# FFT_Device.net
KiCad netlist of a schematic drawn in Altium Designer
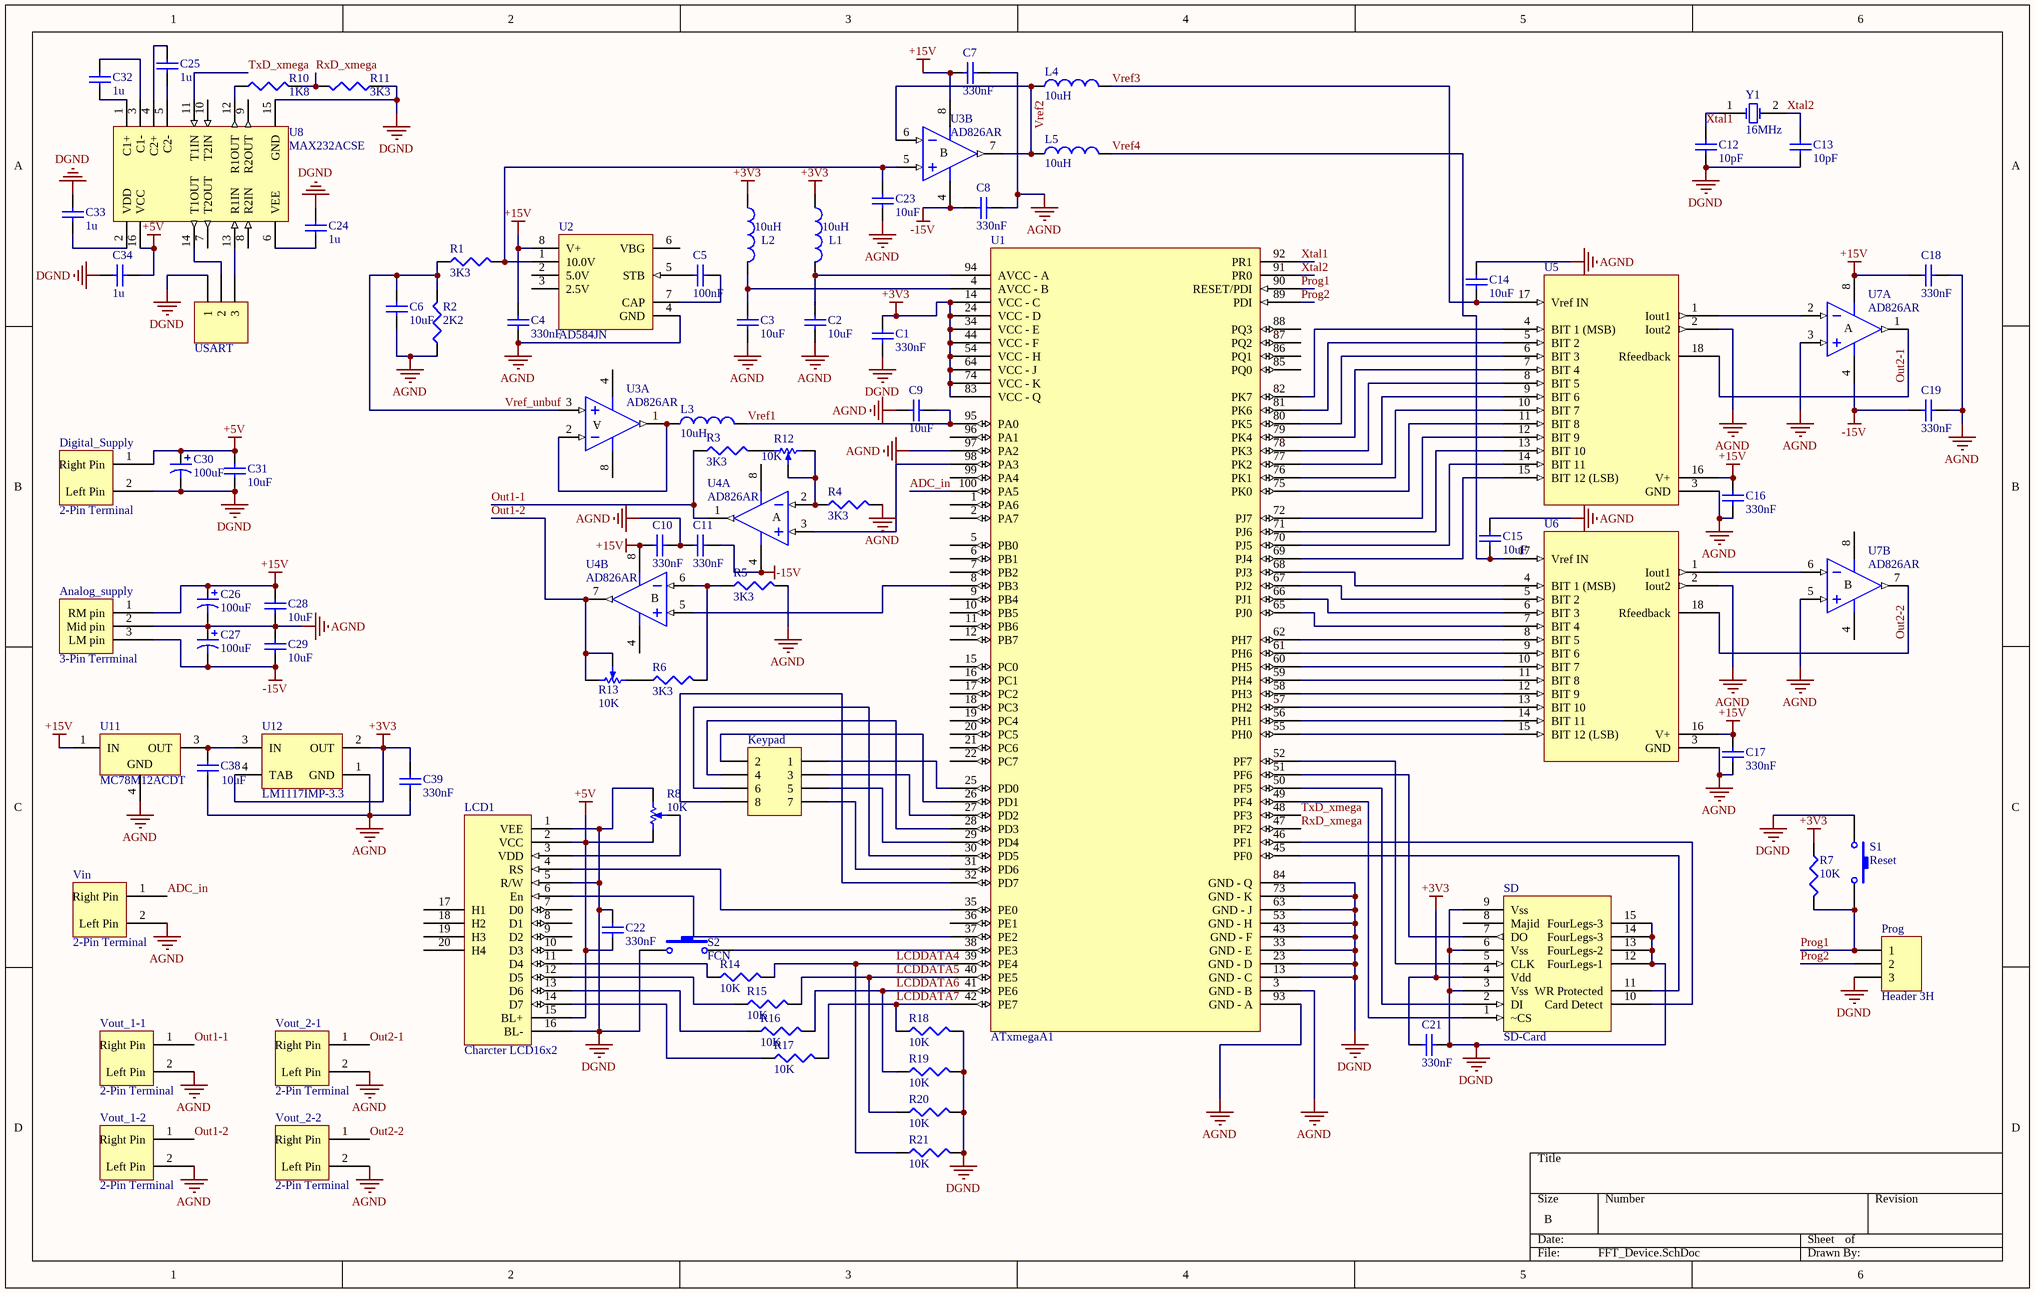
[diagram p0: FFT_Device.SchDoc]

(export (version "E")
  (design (tool "Eeschema 10.0.6"))
  (components
    (comp (ref "Analog_supply")
      (value "3-Pin Terrminal")
      (footprint "3-pin Terminal")
      (libsource (lib "MyLib") (part "3-Pin Terrminal"))
    )
    (comp (ref "C1")
      (value "330nF")
      (footprint "MELF-R3216-1206")
      (description "Capacitor (Semiconductor SIM Model)")
      (fields (field (name "Comment") "Cap Semi"))
      (libsource (lib "Miscellaneous Devices") (part "Cap Semi"))
    )
    (comp (ref "C2")
      (value "10uF")
      (footprint "MELF-R3216-1206")
      (description "Capacitor (Semiconductor SIM Model)")
      (fields (field (name "Comment") "Cap Semi"))
      (libsource (lib "Miscellaneous Devices") (part "Cap Semi"))
    )
    (comp (ref "C3")
      (value "10uF")
      (footprint "MELF-R3216-1206")
      (description "Capacitor (Semiconductor SIM Model)")
      (fields (field (name "Comment") "Cap Semi"))
      (libsource (lib "Miscellaneous Devices") (part "Cap Semi"))
    )
    (comp (ref "C4")
      (value "330nF")
      (footprint "MELF-R3216-1206")
      (description "Capacitor (Semiconductor SIM Model)")
      (fields (field (name "Comment") "Cap Semi"))
      (libsource (lib "") (part "Cap Semi_1"))
    )
    (comp (ref "C5")
      (value "100nF")
      (footprint "MELF-R3216-1206")
      (description "Capacitor (Semiconductor SIM Model)")
      (fields (field (name "Comment") "Cap Semi"))
      (libsource (lib "Miscellaneous Devices") (part "Cap Semi"))
    )
    (comp (ref "C6")
      (value "10uF")
      (footprint "MELF-R3216-1206")
      (description "Capacitor (Semiconductor SIM Model)")
      (fields (field (name "Comment") "Cap Semi"))
      (libsource (lib "") (part "Cap Semi_1"))
    )
    (comp (ref "C7")
      (value "330nF")
      (footprint "MELF-R3216-1206")
      (description "Capacitor (Semiconductor SIM Model)")
      (fields (field (name "Comment") "Cap Semi"))
      (libsource (lib "Miscellaneous Devices") (part "Cap Semi"))
    )
    (comp (ref "C8")
      (value "330nF")
      (footprint "MELF-R3216-1206")
      (description "Capacitor (Semiconductor SIM Model)")
      (fields (field (name "Comment") "Cap Semi"))
      (libsource (lib "Miscellaneous Devices") (part "Cap Semi"))
    )
    (comp (ref "C9")
      (value "10uF")
      (footprint "MELF-R3216-1206")
      (description "Capacitor (Semiconductor SIM Model)")
      (fields (field (name "Comment") "Cap Semi"))
      (libsource (lib "Miscellaneous Devices") (part "Cap Semi"))
    )
    (comp (ref "C10")
      (value "330nF")
      (footprint "MELF-R3216-1206")
      (description "Capacitor (Semiconductor SIM Model)")
      (fields (field (name "Comment") "Cap Semi"))
      (libsource (lib "Miscellaneous Devices") (part "Cap Semi"))
    )
    (comp (ref "C11")
      (value "330nF")
      (footprint "MELF-R3216-1206")
      (description "Capacitor (Semiconductor SIM Model)")
      (fields (field (name "Comment") "Cap Semi"))
      (libsource (lib "Miscellaneous Devices") (part "Cap Semi"))
    )
    (comp (ref "C12")
      (value "10pF")
      (footprint "MELF-R3216-1206")
      (description "Capacitor (Semiconductor SIM Model)")
      (fields (field (name "Comment") "Cap Semi"))
      (libsource (lib "Miscellaneous Devices") (part "Cap Semi"))
    )
    (comp (ref "C13")
      (value "10pF")
      (footprint "MELF-R3216-1206")
      (description "Capacitor (Semiconductor SIM Model)")
      (fields (field (name "Comment") "Cap Semi"))
      (libsource (lib "Miscellaneous Devices") (part "Cap Semi"))
    )
    (comp (ref "C14")
      (value "10uF")
      (footprint "MELF-R3216-1206")
      (description "Capacitor (Semiconductor SIM Model)")
      (fields (field (name "Comment") "Cap Semi"))
      (libsource (lib "") (part "Cap Semi_1"))
    )
    (comp (ref "C15")
      (value "10uF")
      (footprint "MELF-R3216-1206")
      (description "Capacitor (Semiconductor SIM Model)")
      (fields (field (name "Comment") "Cap Semi"))
      (libsource (lib "") (part "Cap Semi_1"))
    )
    (comp (ref "C16")
      (value "330nF")
      (footprint "MELF-R3216-1206")
      (description "Capacitor (Semiconductor SIM Model)")
      (fields (field (name "Comment") "Cap Semi"))
      (libsource (lib "Miscellaneous Devices") (part "Cap Semi"))
    )
    (comp (ref "C17")
      (value "330nF")
      (footprint "MELF-R3216-1206")
      (description "Capacitor (Semiconductor SIM Model)")
      (fields (field (name "Comment") "Cap Semi"))
      (libsource (lib "Miscellaneous Devices") (part "Cap Semi"))
    )
    (comp (ref "C18")
      (value "330nF")
      (footprint "MELF-R3216-1206")
      (description "Capacitor (Semiconductor SIM Model)")
      (fields (field (name "Comment") "Cap Semi"))
      (libsource (lib "Miscellaneous Devices") (part "Cap Semi"))
    )
    (comp (ref "C19")
      (value "330nF")
      (footprint "MELF-R3216-1206")
      (description "Capacitor (Semiconductor SIM Model)")
      (fields (field (name "Comment") "Cap Semi"))
      (libsource (lib "Miscellaneous Devices") (part "Cap Semi"))
    )
    (comp (ref "C21")
      (value "330nF")
      (footprint "MELF-R3216-1206")
      (description "Capacitor (Semiconductor SIM Model)")
      (fields (field (name "Comment") "Cap Semi"))
      (libsource (lib "Miscellaneous Devices") (part "Cap Semi"))
    )
    (comp (ref "C22")
      (value "330nF")
      (footprint "MELF-R3216-1206")
      (description "Capacitor (Semiconductor SIM Model)")
      (fields (field (name "Comment") "Cap Semi"))
      (libsource (lib "Miscellaneous Devices") (part "Cap Semi"))
    )
    (comp (ref "C23")
      (value "10uF")
      (footprint "MELF-R3216-1206")
      (description "Capacitor (Semiconductor SIM Model)")
      (fields (field (name "Comment") "Cap Semi"))
      (libsource (lib "") (part "Cap Semi_1"))
    )
    (comp (ref "C24")
      (value "1u")
      (footprint "MELF-R3216-1206")
      (description "Capacitor (Semiconductor SIM Model)")
      (fields (field (name "Comment") "Cap Semi"))
      (libsource (lib "Miscellaneous Devices") (part "Cap Semi"))
    )
    (comp (ref "C25")
      (value "1u")
      (footprint "MELF-R3216-1206")
      (description "Capacitor (Semiconductor SIM Model)")
      (fields (field (name "Comment") "Cap Semi"))
      (libsource (lib "Miscellaneous Devices") (part "Cap Semi"))
    )
    (comp (ref "C26") (value "100uF") (footprint "Cap Pole-100u") (libsource (lib "MyLib") (part "Cap Pole")))
    (comp (ref "C27") (value "100uF") (footprint "Cap Pole-100u") (libsource (lib "MyLib") (part "Cap Pole")))
    (comp (ref "C28")
      (value "10uF")
      (footprint "CAPTANT100u")
      (description "Capacitor (Semiconductor SIM Model)")
      (fields (field (name "Comment") "Cap Semi"))
      (libsource (lib "Miscellaneous Devices") (part "Cap Semi"))
    )
    (comp (ref "C29")
      (value "10uF")
      (footprint "CAPTANT100u")
      (description "Capacitor (Semiconductor SIM Model)")
      (fields (field (name "Comment") "Cap Semi"))
      (libsource (lib "Miscellaneous Devices") (part "Cap Semi"))
    )
    (comp (ref "C30") (value "100uF") (footprint "Cap Pole-100u") (libsource (lib "MyLib") (part "Cap Pole")))
    (comp (ref "C31")
      (value "10uF")
      (footprint "CAPTANT100u")
      (description "Capacitor (Semiconductor SIM Model)")
      (fields (field (name "Comment") "Cap Semi"))
      (libsource (lib "Miscellaneous Devices") (part "Cap Semi"))
    )
    (comp (ref "C32")
      (value "1u")
      (footprint "MELF-R3216-1206")
      (description "Capacitor (Semiconductor SIM Model)")
      (fields (field (name "Comment") "Cap Semi"))
      (libsource (lib "Miscellaneous Devices") (part "Cap Semi"))
    )
    (comp (ref "C33")
      (value "1u")
      (footprint "MELF-R3216-1206")
      (description "Capacitor (Semiconductor SIM Model)")
      (fields (field (name "Comment") "Cap Semi"))
      (libsource (lib "Miscellaneous Devices") (part "Cap Semi"))
    )
    (comp (ref "C34")
      (value "1u")
      (footprint "MELF-R3216-1206")
      (description "Capacitor (Semiconductor SIM Model)")
      (fields (field (name "Comment") "Cap Semi"))
      (libsource (lib "Miscellaneous Devices") (part "Cap Semi"))
    )
    (comp (ref "C38")
      (value "10uF")
      (footprint "MELF-R3216-1206")
      (description "Capacitor (Semiconductor SIM Model)")
      (fields (field (name "Comment") "Cap Semi"))
      (libsource (lib "Miscellaneous Devices") (part "Cap Semi"))
    )
    (comp (ref "C39")
      (value "330nF")
      (footprint "MELF-R3216-1206")
      (description "Capacitor (Semiconductor SIM Model)")
      (fields (field (name "Comment") "Cap Semi"))
      (libsource (lib "Miscellaneous Devices") (part "Cap Semi"))
    )
    (comp (ref "Digital_Supply")
      (value "2-Pin Terminal")
      (footprint "2-pin Terminal")
      (libsource (lib "MyLib") (part "2-Pin Terminal"))
    )
    (comp (ref "Keypad")
      (value "Header 4X2")
      (footprint "HDR2X4")
      (description "Header, 4-Pin, Dual row")
      (libsource (lib "Miscellaneous Connectors") (part "Header 4X2"))
    )
    (comp (ref "L1")
      (value "10uH")
      (footprint "MELF-R3216-1206")
      (description "Inductor")
      (libsource (lib "") (part "Inductor_1"))
    )
    (comp (ref "L2")
      (value "10uH")
      (footprint "MELF-R3216-1206")
      (description "Inductor")
      (libsource (lib "") (part "Inductor_1"))
    )
    (comp (ref "L3")
      (value "10uH")
      (footprint "MELF-R3216-1206")
      (description "Inductor")
      (libsource (lib "Miscellaneous Devices") (part "Inductor"))
    )
    (comp (ref "L4")
      (value "10uH")
      (footprint "MELF-R3216-1206")
      (description "Inductor")
      (libsource (lib "Miscellaneous Devices") (part "Inductor"))
    )
    (comp (ref "L5")
      (value "10uH")
      (footprint "MELF-R3216-1206")
      (description "Inductor")
      (libsource (lib "Miscellaneous Devices") (part "Inductor"))
    )
    (comp (ref "LCD1")
      (value "Charcter LCD16x2")
      (footprint "LCD16x2")
      (libsource (lib "MyLib") (part "LCD16x2"))
    )
    (comp (ref "Prog")
      (value "Header 3H")
      (footprint "HDR1X3H")
      (description "Header, 3-Pin, Right Angle")
      (libsource (lib "Miscellaneous Connectors") (part "Header 3H"))
    )
    (comp (ref "R1")
      (value "3K3")
      (footprint "MELF-R3216-1206")
      (description "Resistor")
      (fields (field (name "Comment") "Res3"))
      (libsource (lib "Miscellaneous Devices") (part "Res3"))
    )
    (comp (ref "R2")
      (value "2K2")
      (footprint "MELF-R3216-1206")
      (description "Resistor")
      (fields (field (name "Comment") "Res3"))
      (libsource (lib "Miscellaneous Devices") (part "Res3"))
    )
    (comp (ref "R3")
      (value "3K3")
      (footprint "MELF-R3216-1206")
      (description "Resistor")
      (fields (field (name "Comment") "Res3"))
      (libsource (lib "Miscellaneous Devices") (part "Res3"))
    )
    (comp (ref "R4")
      (value "3K3")
      (footprint "MELF-R3216-1206")
      (description "Resistor")
      (fields (field (name "Comment") "Res3"))
      (libsource (lib "Miscellaneous Devices") (part "Res3"))
    )
    (comp (ref "R5")
      (value "3K3")
      (footprint "MELF-R3216-1206")
      (description "Resistor")
      (fields (field (name "Comment") "Res3"))
      (libsource (lib "Miscellaneous Devices") (part "Res3"))
    )
    (comp (ref "R6")
      (value "3K3")
      (footprint "MELF-R3216-1206")
      (description "Resistor")
      (fields (field (name "Comment") "Res3"))
      (libsource (lib "Miscellaneous Devices") (part "Res3"))
    )
    (comp (ref "R7")
      (value "10K")
      (footprint "MELF-R3216-1206")
      (description "Resistor")
      (fields (field (name "Comment") "Res3"))
      (libsource (lib "Miscellaneous Devices") (part "Res3"))
    )
    (comp (ref "R8")
      (value "10K")
      (footprint "POT4MM-2")
      (description "Square Trimming Potentiometer")
      (libsource (lib "Miscellaneous Devices") (part "RPot SM"))
    )
    (comp (ref "R10")
      (value "1K8")
      (footprint "MELF-R3216-1206")
      (description "Resistor")
      (fields (field (name "Comment") "Res3"))
      (libsource (lib "Miscellaneous Devices") (part "Res3"))
    )
    (comp (ref "R11")
      (value "3K3")
      (footprint "MELF-R3216-1206")
      (description "Resistor")
      (fields (field (name "Comment") "Res3"))
      (libsource (lib "Miscellaneous Devices") (part "Res3"))
    )
    (comp (ref "R12")
      (value "10K")
      (footprint "POT4MM-2")
      (description "Square Trimming Potentiometer")
      (libsource (lib "Miscellaneous Devices") (part "RPot SM"))
    )
    (comp (ref "R13")
      (value "10K")
      (footprint "POT4MM-2")
      (description "Square Trimming Potentiometer")
      (libsource (lib "Miscellaneous Devices") (part "RPot SM"))
    )
    (comp (ref "R14")
      (value "10K")
      (footprint "MELF-R3216-1206")
      (description "Resistor")
      (fields (field (name "Comment") "Res3"))
      (libsource (lib "Miscellaneous Devices") (part "Res3"))
    )
    (comp (ref "R15")
      (value "10K")
      (footprint "MELF-R3216-1206")
      (description "Resistor")
      (fields (field (name "Comment") "Res3"))
      (libsource (lib "Miscellaneous Devices") (part "Res3"))
    )
    (comp (ref "R16")
      (value "10K")
      (footprint "MELF-R3216-1206")
      (description "Resistor")
      (fields (field (name "Comment") "Res3"))
      (libsource (lib "Miscellaneous Devices") (part "Res3"))
    )
    (comp (ref "R17")
      (value "10K")
      (footprint "MELF-R3216-1206")
      (description "Resistor")
      (fields (field (name "Comment") "Res3"))
      (libsource (lib "Miscellaneous Devices") (part "Res3"))
    )
    (comp (ref "R18")
      (value "10K")
      (footprint "MELF-R3216-1206")
      (description "Resistor")
      (fields (field (name "Comment") "Res3"))
      (libsource (lib "Miscellaneous Devices") (part "Res3"))
    )
    (comp (ref "R19")
      (value "10K")
      (footprint "MELF-R3216-1206")
      (description "Resistor")
      (fields (field (name "Comment") "Res3"))
      (libsource (lib "Miscellaneous Devices") (part "Res3"))
    )
    (comp (ref "R20")
      (value "10K")
      (footprint "MELF-R3216-1206")
      (description "Resistor")
      (fields (field (name "Comment") "Res3"))
      (libsource (lib "Miscellaneous Devices") (part "Res3"))
    )
    (comp (ref "R21")
      (value "10K")
      (footprint "MELF-R3216-1206")
      (description "Resistor")
      (fields (field (name "Comment") "Res3"))
      (libsource (lib "Miscellaneous Devices") (part "Res3"))
    )
    (comp (ref "S1")
      (value "Reset")
      (footprint "SMD_Switch")
      (description "Switch")
      (libsource (lib "") (part "SW-PB_1"))
    )
    (comp (ref "S2")
      (value "FCN")
      (footprint "SMD_Switch")
      (description "Switch")
      (libsource (lib "Miscellaneous Devices") (part "SW-PB"))
    )
    (comp (ref "SD")
      (value "SD-Card")
      (footprint "SD-Card-Socket")
      (libsource (lib "MyLib") (part "SD-Card"))
    )
    (comp (ref "U1")
      (value "ATxmegaA1")
      (footprint "TQFP100")
      (description "High Performance 8/16bit MCU")
      (libsource (lib "MyLib") (part "ATxMega_A1"))
    )
    (comp (ref "U2")
      (value "AD584JN")
      (footprint "N-8")
      (description "10V, 7.5V, 5V, 2.5V Pin Programmable Precision Voltage Reference")
      (libsource (lib "AD Power Mgt Voltage Reference") (part "AD584JN"))
    )
    (comp (ref "U3")
      (value "AD826AR")
      (footprint "R-8D_N")
      (description "High-Speed, Low-Power Dual Operational Amplifier")
      (libsource (lib "AD Operational Amplifier") (part "AD826AR"))
    )
    (comp (ref "U4")
      (value "AD826AR")
      (footprint "R-8D_N")
      (description "High-Speed, Low-Power Dual Operational Amplifier")
      (libsource (lib "AD Operational Amplifier") (part "AD826AR"))
    )
    (comp (ref "U5") (value "DAC") (footprint "DIP-18/D23") (libsource (lib "MyLib") (part "AD7541")))
    (comp (ref "U6") (value "DAC") (footprint "DIP-18/D23") (libsource (lib "MyLib") (part "AD7541")))
    (comp (ref "U7")
      (value "AD826AR")
      (footprint "R-8D_N")
      (description "High-Speed, Low-Power Dual Operational Amplifier")
      (libsource (lib "AD Operational Amplifier") (part "AD826AR"))
    )
    (comp (ref "U8")
      (value "MAX232ACSE")
      (footprint "NSO16_N")
      (description "+5V Powered, Multi-Channel RS-232 Driver/Receiver")
      (libsource (lib "Maxim Communication Transceiver") (part "MAX232ACSE"))
    )
    (comp (ref "U11")
      (value "MC78M12ACDT")
      (footprint "369A-13")
      (description "Three-Terminal Medium Current Positive Voltage Regulator")
      (libsource (lib "ON Semi Power Mgt Voltage Regulator") (part "MC78M12ACDT"))
    )
    (comp (ref "U12")
      (value "LM1117IMP-3.3")
      (footprint "MP04A_L")
      (description "800mA Low-Dropout Linear Regulator")
      (fields
        (field (name "MANUFACTURER") "National Semiconductor")
        (field (name "DIGIKEYPARTNUMBER") "LM1117IMP-3.3CT-ND")
      )
      (libsource (lib "NSC LDO") (part "LM1117IMP-3.3"))
    )
    (comp (ref "USART")
      (value "Header 3")
      (footprint "HDR1X3")
      (description "Header, 3-Pin")
      (libsource (lib "Miscellaneous Connectors") (part "Header 3"))
    )
    (comp (ref "Vin")
      (value "2-Pin Terminal")
      (footprint "2-pin Terminal")
      (libsource (lib "MyLib") (part "2-Pin Terminal"))
    )
    (comp (ref "Vout_1-1")
      (value "2-Pin Terminal")
      (footprint "2-pin Terminal")
      (libsource (lib "MyLib") (part "2-Pin Terminal"))
    )
    (comp (ref "Vout_1-2")
      (value "2-Pin Terminal")
      (footprint "2-pin Terminal")
      (libsource (lib "MyLib") (part "2-Pin Terminal"))
    )
    (comp (ref "Vout_2-1")
      (value "2-Pin Terminal")
      (footprint "2-pin Terminal")
      (libsource (lib "MyLib") (part "2-Pin Terminal"))
    )
    (comp (ref "Vout_2-2")
      (value "2-Pin Terminal")
      (footprint "2-pin Terminal")
      (libsource (lib "MyLib") (part "2-Pin Terminal"))
    )
    (comp (ref "Y1")
      (value "16MHz")
      (footprint "HC-49U")
      (description "Crystal Oscillator")
      (libsource (lib "ECS Crystal Oscillator") (part "ECS-10-13-1"))
    )
  )
  (nets
    (net (code "1") (name "+3V3") (class "Default")
      (node (ref "C1") (pin "1") (pinfunction "1_1") (pintype "passive"))
      (node (ref "C21") (pin "2") (pinfunction "2_2") (pintype "passive"))
      (node (ref "C39") (pin "2") (pinfunction "2_2") (pintype "passive"))
      (node (ref "L1") (pin "2") (pinfunction "2_2") (pintype "passive"))
      (node (ref "L2") (pin "2") (pinfunction "2_2") (pintype "passive"))
      (node (ref "R7") (pin "1") (pinfunction "1_1") (pintype "passive"))
      (node (ref "SD") (pin "4") (pinfunction "Vdd_4") (pintype "power_in"))
      (node (ref "U1") (pin "14") (pinfunction "VCC_-_C_14") (pintype "power_in"))
      (node (ref "U1") (pin "24") (pinfunction "VCC_-_D_24") (pintype "power_in"))
      (node (ref "U1") (pin "34") (pinfunction "VCC_-_E_34") (pintype "power_in"))
      (node (ref "U1") (pin "44") (pinfunction "VCC_-_F_44") (pintype "power_in"))
      (node (ref "U1") (pin "54") (pinfunction "VCC_-_H_54") (pintype "power_in"))
      (node (ref "U1") (pin "64") (pinfunction "VCC_-_J_64") (pintype "power_in"))
      (node (ref "U1") (pin "74") (pinfunction "VCC_-_K_74") (pintype "power_in"))
      (node (ref "U1") (pin "83") (pinfunction "VCC_-_Q_83") (pintype "power_in"))
      (node (ref "U12") (pin "2") (pinfunction "OUT_2") (pintype "power_in"))
      (node (ref "U12") (pin "4") (pinfunction "TAB_4") (pintype "power_in"))
    )
    (net (code "2") (name "+5V") (class "Default")
      (node (ref "C22") (pin "1") (pinfunction "1_1") (pintype "passive"))
      (node (ref "C30") (pin "1") (pinfunction "1_1") (pintype "passive"))
      (node (ref "C31") (pin "2") (pinfunction "2_2") (pintype "passive"))
      (node (ref "C34") (pin "1") (pinfunction "1_1") (pintype "passive"))
      (node (ref "Digital_Supply") (pin "1") (pinfunction "Right_Pin_1") (pintype "power_in"))
      (node (ref "LCD1") (pin "15") (pinfunction "BL+_15") (pintype "passive"))
      (node (ref "LCD1") (pin "2") (pinfunction "VCC_2") (pintype "power_in"))
      (node (ref "R8") (pin "CCW") (pinfunction "-_CCW") (pintype "passive"))
      (node (ref "U8") (pin "16") (pinfunction "VCC_16") (pintype "power_in"))
    )
    (net (code "3") (name "+15V") (class "Default")
      (node (ref "Analog_supply") (pin "1") (pinfunction "RM_pin_1") (pintype "power_in"))
      (node (ref "C10") (pin "2") (pinfunction "2_2") (pintype "passive"))
      (node (ref "C16") (pin "2") (pinfunction "2_2") (pintype "passive"))
      (node (ref "C17") (pin "2") (pinfunction "2_2") (pintype "passive"))
      (node (ref "C18") (pin "1") (pinfunction "1_1") (pintype "passive"))
      (node (ref "C26") (pin "1") (pinfunction "1_1") (pintype "passive"))
      (node (ref "C28") (pin "2") (pinfunction "2_2") (pintype "passive"))
      (node (ref "C4") (pin "2") (pinfunction "2_2") (pintype "passive"))
      (node (ref "C7") (pin "2") (pinfunction "2_2") (pintype "passive"))
      (node (ref "U11") (pin "1") (pinfunction "IN_1") (pintype "power_in"))
      (node (ref "U2") (pin "8") (pinfunction "V+_8") (pintype "power_in"))
      (node (ref "U3") (pin "8") (pinfunction "V+_8") (pintype "power_in"))
      (node (ref "U4") (pin "8") (pinfunction "V+_8") (pintype "power_in"))
      (node (ref "U5") (pin "16") (pinfunction "V+_16") (pintype "power_in"))
      (node (ref "U6") (pin "16") (pinfunction "V+_16") (pintype "power_in"))
      (node (ref "U7") (pin "8") (pinfunction "V+_8") (pintype "power_in"))
    )
    (net (code "4") (name "-15V") (class "Default")
      (node (ref "Analog_supply") (pin "3") (pinfunction "LM_pin_3") (pintype "power_in"))
      (node (ref "C11") (pin "1") (pinfunction "1_1") (pintype "passive"))
      (node (ref "C19") (pin "1") (pinfunction "1_1") (pintype "passive"))
      (node (ref "C27") (pin "2") (pinfunction "2_2") (pintype "passive"))
      (node (ref "C29") (pin "1") (pinfunction "1_1") (pintype "passive"))
      (node (ref "C8") (pin "1") (pinfunction "1_1") (pintype "passive"))
      (node (ref "U3") (pin "4") (pinfunction "V-_4") (pintype "power_in"))
      (node (ref "U4") (pin "4") (pinfunction "V-_4") (pintype "power_in"))
      (node (ref "U7") (pin "4") (pinfunction "V-_4") (pintype "power_in"))
    )
    (net (code "5") (name "/ADC_in") (class "Default")
      (node (ref "U1") (pin "100") (pinfunction "PA5_100") (pintype "bidirectional"))
      (node (ref "Vin") (pin "1") (pinfunction "Right_Pin_1") (pintype "power_in"))
    )
    (net (code "6") (name "/LCDDATA4") (class "Default")
      (node (ref "R14") (pin "1") (pinfunction "1_1") (pintype "passive"))
      (node (ref "R21") (pin "2") (pinfunction "2_2") (pintype "passive"))
      (node (ref "U1") (pin "39") (pinfunction "PE4_39") (pintype "bidirectional"))
    )
    (net (code "7") (name "/LCDDATA5") (class "Default")
      (node (ref "R15") (pin "1") (pinfunction "1_1") (pintype "passive"))
      (node (ref "R20") (pin "2") (pinfunction "2_2") (pintype "passive"))
      (node (ref "U1") (pin "40") (pinfunction "PE5_40") (pintype "bidirectional"))
    )
    (net (code "8") (name "/LCDDATA6") (class "Default")
      (node (ref "R16") (pin "1") (pinfunction "1_1") (pintype "passive"))
      (node (ref "R19") (pin "2") (pinfunction "2_2") (pintype "passive"))
      (node (ref "U1") (pin "41") (pinfunction "PE6_41") (pintype "bidirectional"))
    )
    (net (code "9") (name "/LCDDATA7") (class "Default")
      (node (ref "R17") (pin "1") (pinfunction "1_1") (pintype "passive"))
      (node (ref "R18") (pin "2") (pinfunction "2_2") (pintype "passive"))
      (node (ref "U1") (pin "42") (pinfunction "PE7_42") (pintype "bidirectional"))
    )
    (net (code "10") (name "/Out1-1") (class "Default")
      (node (ref "R3") (pin "2") (pinfunction "2_2") (pintype "passive"))
      (node (ref "U4") (pin "1") (pinfunction "OUT_1") (pintype "output"))
      (node (ref "Vout_1-1") (pin "1") (pinfunction "Right_Pin_1") (pintype "power_in"))
    )
    (net (code "11") (name "/Out1-2") (class "Default")
      (node (ref "R13") (pin "CW") (pinfunction "+_CW") (pintype "passive"))
      (node (ref "R13") (pin "W") (pinfunction "W_W") (pintype "passive"))
      (node (ref "U4") (pin "7") (pinfunction "OUT_7") (pintype "output"))
      (node (ref "Vout_1-2") (pin "1") (pinfunction "Right_Pin_1") (pintype "power_in"))
    )
    (net (code "12") (name "/Out2-1") (class "Default")
      (node (ref "U5") (pin "18") (pinfunction "Rfeedback_18") (pintype "passive"))
      (node (ref "U7") (pin "1") (pinfunction "OUT_1") (pintype "output"))
      (node (ref "Vout_2-1") (pin "1") (pinfunction "Right_Pin_1") (pintype "power_in"))
    )
    (net (code "13") (name "/Out2-2") (class "Default")
      (node (ref "U6") (pin "18") (pinfunction "Rfeedback_18") (pintype "passive"))
      (node (ref "U7") (pin "7") (pinfunction "OUT_7") (pintype "output"))
      (node (ref "Vout_2-2") (pin "1") (pinfunction "Right_Pin_1") (pintype "power_in"))
    )
    (net (code "14") (name "/Prog1") (class "Default")
      (node (ref "Prog") (pin "1") (pinfunction "1_1") (pintype "passive"))
      (node (ref "R7") (pin "2") (pinfunction "2_2") (pintype "passive"))
      (node (ref "S1") (pin "1") (pinfunction "1_1") (pintype "passive"))
      (node (ref "U1") (pin "90") (pinfunction "RESET/PDI_90") (pintype "input"))
    )
    (net (code "15") (name "/Prog2") (class "Default")
      (node (ref "Prog") (pin "2") (pinfunction "2_2") (pintype "passive"))
      (node (ref "U1") (pin "89") (pinfunction "PDI_89") (pintype "input"))
    )
    (net (code "16") (name "/RxD_xmega") (class "Default")
      (node (ref "R10") (pin "2") (pinfunction "2_2") (pintype "passive"))
      (node (ref "R11") (pin "2") (pinfunction "2_2") (pintype "passive"))
      (node (ref "U1") (pin "47") (pinfunction "PF2_47") (pintype "bidirectional"))
    )
    (net (code "17") (name "/TxD_xmega") (class "Default")
      (node (ref "U1") (pin "48") (pinfunction "PF3_48") (pintype "bidirectional"))
      (node (ref "U8") (pin "11") (pinfunction "T1IN_11") (pintype "input"))
    )
    (net (code "18") (name "/Vref1") (class "Default")
      (node (ref "C9") (pin "1") (pinfunction "1_1") (pintype "passive"))
      (node (ref "L3") (pin "1") (pinfunction "1_1") (pintype "passive"))
      (node (ref "U1") (pin "95") (pinfunction "PA0_95") (pintype "bidirectional"))
    )
    (net (code "19") (name "/Vref2") (class "Default")
      (node (ref "L4") (pin "2") (pinfunction "2_2") (pintype "passive"))
      (node (ref "L5") (pin "2") (pinfunction "2_2") (pintype "passive"))
      (node (ref "U3") (pin "6") (pinfunction "IN-_6") (pintype "input"))
      (node (ref "U3") (pin "7") (pinfunction "OUT_7") (pintype "output"))
    )
    (net (code "20") (name "/Vref3") (class "Default")
      (node (ref "C14") (pin "2") (pinfunction "2_2") (pintype "passive"))
      (node (ref "L4") (pin "1") (pinfunction "1_1") (pintype "passive"))
      (node (ref "U5") (pin "17") (pinfunction "Vref_IN_17") (pintype "input"))
    )
    (net (code "21") (name "/Vref4") (class "Default")
      (node (ref "C15") (pin "2") (pinfunction "2_2") (pintype "passive"))
      (node (ref "L5") (pin "1") (pinfunction "1_1") (pintype "passive"))
      (node (ref "U6") (pin "17") (pinfunction "Vref_IN_17") (pintype "input"))
    )
    (net (code "22") (name "/Vref_unbuf") (class "Default")
      (node (ref "C6") (pin "2") (pinfunction "2_2") (pintype "passive"))
      (node (ref "R1") (pin "2") (pinfunction "2_2") (pintype "passive"))
      (node (ref "R2") (pin "1") (pinfunction "1_1") (pintype "passive"))
      (node (ref "U3") (pin "3") (pinfunction "IN+_3") (pintype "input"))
    )
    (net (code "23") (name "/Xtal1") (class "Default")
      (node (ref "C12") (pin "1") (pinfunction "1_1") (pintype "passive"))
      (node (ref "U1") (pin "92") (pinfunction "PR1_92") (pintype "power_in"))
      (node (ref "Y1") (pin "1") (pinfunction "OSC1_1") (pintype "passive"))
    )
    (net (code "24") (name "/Xtal2") (class "Default")
      (node (ref "C13") (pin "2") (pinfunction "2_2") (pintype "passive"))
      (node (ref "U1") (pin "91") (pinfunction "PR0_91") (pintype "power_in"))
      (node (ref "Y1") (pin "2") (pinfunction "OSC2_2") (pintype "passive"))
    )
    (net (code "25") (name "AGND") (class "Default")
      (node (ref "Analog_supply") (pin "2") (pinfunction "Mid_pin_2") (pintype "power_in"))
      (node (ref "C10") (pin "1") (pinfunction "1_1") (pintype "passive"))
      (node (ref "C11") (pin "2") (pinfunction "2_2") (pintype "passive"))
      (node (ref "C14") (pin "1") (pinfunction "1_1") (pintype "passive"))
      (node (ref "C15") (pin "1") (pinfunction "1_1") (pintype "passive"))
      (node (ref "C16") (pin "1") (pinfunction "1_1") (pintype "passive"))
      (node (ref "C17") (pin "1") (pinfunction "1_1") (pintype "passive"))
      (node (ref "C18") (pin "2") (pinfunction "2_2") (pintype "passive"))
      (node (ref "C19") (pin "2") (pinfunction "2_2") (pintype "passive"))
      (node (ref "C2") (pin "1") (pinfunction "1_1") (pintype "passive"))
      (node (ref "C23") (pin "1") (pinfunction "1_1") (pintype "passive"))
      (node (ref "C26") (pin "2") (pinfunction "2_2") (pintype "passive"))
      (node (ref "C27") (pin "1") (pinfunction "1_1") (pintype "passive"))
      (node (ref "C28") (pin "1") (pinfunction "1_1") (pintype "passive"))
      (node (ref "C29") (pin "2") (pinfunction "2_2") (pintype "passive"))
      (node (ref "C3") (pin "1") (pinfunction "1_1") (pintype "passive"))
      (node (ref "C38") (pin "1") (pinfunction "1_1") (pintype "passive"))
      (node (ref "C39") (pin "1") (pinfunction "1_1") (pintype "passive"))
      (node (ref "C4") (pin "1") (pinfunction "1_1") (pintype "passive"))
      (node (ref "C6") (pin "1") (pinfunction "1_1") (pintype "passive"))
      (node (ref "C7") (pin "1") (pinfunction "1_1") (pintype "passive"))
      (node (ref "C8") (pin "2") (pinfunction "2_2") (pintype "passive"))
      (node (ref "C9") (pin "2") (pinfunction "2_2") (pintype "passive"))
      (node (ref "R2") (pin "2") (pinfunction "2_2") (pintype "passive"))
      (node (ref "R4") (pin "1") (pinfunction "1_1") (pintype "passive"))
      (node (ref "R5") (pin "1") (pinfunction "1_1") (pintype "passive"))
      (node (ref "U1") (pin "3") (pinfunction "GND_-_B_3") (pintype "power_in"))
      (node (ref "U1") (pin "93") (pinfunction "GND_-_A_93") (pintype "power_in"))
      (node (ref "U1") (pin "97") (pinfunction "PA2_97") (pintype "bidirectional"))
      (node (ref "U11") (pin "4") (pinfunction "GND_4") (pintype "power_in"))
      (node (ref "U12") (pin "1") (pinfunction "GND_1") (pintype "power_in"))
      (node (ref "U2") (pin "4") (pinfunction "GND_4") (pintype "power_in"))
      (node (ref "U5") (pin "2") (pinfunction "Iout2_2") (pintype "output"))
      (node (ref "U5") (pin "3") (pinfunction "GND_3") (pintype "power_in"))
      (node (ref "U6") (pin "2") (pinfunction "Iout2_2") (pintype "output"))
      (node (ref "U6") (pin "3") (pinfunction "GND_3") (pintype "power_in"))
      (node (ref "U7") (pin "3") (pinfunction "IN+_3") (pintype "input"))
      (node (ref "U7") (pin "5") (pinfunction "IN+_5") (pintype "input"))
      (node (ref "Vin") (pin "2") (pinfunction "Left_Pin_2") (pintype "power_in"))
      (node (ref "Vout_1-1") (pin "2") (pinfunction "Left_Pin_2") (pintype "power_in"))
      (node (ref "Vout_1-2") (pin "2") (pinfunction "Left_Pin_2") (pintype "power_in"))
      (node (ref "Vout_2-1") (pin "2") (pinfunction "Left_Pin_2") (pintype "power_in"))
      (node (ref "Vout_2-2") (pin "2") (pinfunction "Left_Pin_2") (pintype "power_in"))
    )
    (net (code "26") (name "DGND") (class "Default")
      (node (ref "C1") (pin "2") (pinfunction "2_2") (pintype "passive"))
      (node (ref "C12") (pin "2") (pinfunction "2_2") (pintype "passive"))
      (node (ref "C13") (pin "1") (pinfunction "1_1") (pintype "passive"))
      (node (ref "C21") (pin "1") (pinfunction "1_1") (pintype "passive"))
      (node (ref "C22") (pin "2") (pinfunction "2_2") (pintype "passive"))
      (node (ref "C24") (pin "2") (pinfunction "2_2") (pintype "passive"))
      (node (ref "C30") (pin "2") (pinfunction "2_2") (pintype "passive"))
      (node (ref "C31") (pin "1") (pinfunction "1_1") (pintype "passive"))
      (node (ref "C33") (pin "1") (pinfunction "1_1") (pintype "passive"))
      (node (ref "C34") (pin "2") (pinfunction "2_2") (pintype "passive"))
      (node (ref "Digital_Supply") (pin "2") (pinfunction "Left_Pin_2") (pintype "power_in"))
      (node (ref "LCD1") (pin "1") (pinfunction "VEE_1") (pintype "power_in"))
      (node (ref "LCD1") (pin "16") (pinfunction "BL-_16") (pintype "passive"))
      (node (ref "LCD1") (pin "5") (pinfunction "R/W_5") (pintype "input"))
      (node (ref "Prog") (pin "3") (pinfunction "3_3") (pintype "passive"))
      (node (ref "R11") (pin "1") (pinfunction "1_1") (pintype "passive"))
      (node (ref "R18") (pin "1") (pinfunction "1_1") (pintype "passive"))
      (node (ref "R19") (pin "1") (pinfunction "1_1") (pintype "passive"))
      (node (ref "R20") (pin "1") (pinfunction "1_1") (pintype "passive"))
      (node (ref "R21") (pin "1") (pinfunction "1_1") (pintype "passive"))
      (node (ref "R8") (pin "CW") (pinfunction "+_CW") (pintype "passive"))
      (node (ref "S1") (pin "2") (pinfunction "2_2") (pintype "passive"))
      (node (ref "S2") (pin "2") (pinfunction "2_2") (pintype "passive"))
      (node (ref "SD") (pin "12") (pinfunction "FourLegs-1_12") (pintype "power_in"))
      (node (ref "SD") (pin "13") (pinfunction "FourLegs-2_13") (pintype "power_in"))
      (node (ref "SD") (pin "14") (pinfunction "FourLegs-3_14") (pintype "power_in"))
      (node (ref "SD") (pin "15") (pinfunction "FourLegs-3_15") (pintype "power_in"))
      (node (ref "SD") (pin "3") (pinfunction "Vss_3") (pintype "power_in"))
      (node (ref "SD") (pin "6") (pinfunction "Vss_6") (pintype "power_in"))
      (node (ref "SD") (pin "9") (pinfunction "Vss_9") (pintype "power_in"))
      (node (ref "U1") (pin "13") (pinfunction "GND_-_C_13") (pintype "power_in"))
      (node (ref "U1") (pin "23") (pinfunction "GND_-_D_23") (pintype "power_in"))
      (node (ref "U1") (pin "33") (pinfunction "GND_-_E_33") (pintype "power_in"))
      (node (ref "U1") (pin "43") (pinfunction "GND_-_F_43") (pintype "power_in"))
      (node (ref "U1") (pin "53") (pinfunction "GND_-_H_53") (pintype "power_in"))
      (node (ref "U1") (pin "63") (pinfunction "GND_-_J_63") (pintype "power_in"))
      (node (ref "U1") (pin "73") (pinfunction "GND_-_K_73") (pintype "power_in"))
      (node (ref "U1") (pin "84") (pinfunction "GND_-_Q_84") (pintype "power_in"))
      (node (ref "U8") (pin "15") (pinfunction "GND_15") (pintype "power_in"))
      (node (ref "USART") (pin "1") (pinfunction "1_1") (pintype "passive"))
    )
    (net (code "27") (name "Net-(LCD1-D4)") (class "Default")
      (node (ref "LCD1") (pin "11") (pinfunction "D4_11") (pintype "bidirectional"))
      (node (ref "R14") (pin "2") (pinfunction "2_2") (pintype "passive"))
    )
    (net (code "28") (name "Net-(LCD1-D5)") (class "Default")
      (node (ref "LCD1") (pin "12") (pinfunction "D5_12") (pintype "bidirectional"))
      (node (ref "R15") (pin "2") (pinfunction "2_2") (pintype "passive"))
    )
    (net (code "29") (name "Net-(LCD1-D6)") (class "Default")
      (node (ref "LCD1") (pin "13") (pinfunction "D6_13") (pintype "bidirectional"))
      (node (ref "R16") (pin "2") (pinfunction "2_2") (pintype "passive"))
    )
    (net (code "30") (name "Net-(LCD1-D7)") (class "Default")
      (node (ref "LCD1") (pin "14") (pinfunction "D7_14") (pintype "bidirectional"))
      (node (ref "R17") (pin "2") (pinfunction "2_2") (pintype "passive"))
    )
    (net (code "31") (name "Net-(LCD1-En)") (class "Default")
      (node (ref "LCD1") (pin "6") (pinfunction "En_6") (pintype "input"))
      (node (ref "U1") (pin "37") (pinfunction "PE2_37") (pintype "bidirectional"))
    )
    (net (code "32") (name "Net-(LCD1-RS)") (class "Default")
      (node (ref "LCD1") (pin "4") (pinfunction "RS_4") (pintype "input"))
      (node (ref "U1") (pin "35") (pinfunction "PE0_35") (pintype "bidirectional"))
    )
    (net (code "33") (name "Net-(LCD1-VDD)") (class "Default")
      (node (ref "LCD1") (pin "3") (pinfunction "VDD_3") (pintype "input"))
      (node (ref "R8") (pin "W") (pinfunction "W_W") (pintype "passive"))
    )
    (net (code "34") (name "Net-(R12-+)") (class "Default")
      (node (ref "R12") (pin "CW") (pinfunction "+_CW") (pintype "passive"))
      (node (ref "R12") (pin "W") (pinfunction "W_W") (pintype "passive"))
      (node (ref "R4") (pin "2") (pinfunction "2_2") (pintype "passive"))
      (node (ref "U4") (pin "2") (pinfunction "IN-_2") (pintype "input"))
    )
    (net (code "35") (name "Net-(R12--)") (class "Default")
      (node (ref "R12") (pin "CCW") (pinfunction "-_CCW") (pintype "passive"))
      (node (ref "R3") (pin "1") (pinfunction "1_1") (pintype "passive"))
    )
    (net (code "36") (name "Net-(R13--)") (class "Default")
      (node (ref "R13") (pin "CCW") (pinfunction "-_CCW") (pintype "passive"))
      (node (ref "R6") (pin "2") (pinfunction "2_2") (pintype "passive"))
    )
    (net (code "37") (name "Net-(SD-CLK)") (class "Default")
      (node (ref "SD") (pin "5") (pinfunction "CLK_5") (pintype "input"))
      (node (ref "U1") (pin "52") (pinfunction "PF7_52") (pintype "bidirectional"))
    )
    (net (code "38") (name "Net-(SD-Card_Detect)") (class "Default")
      (node (ref "SD") (pin "10") (pinfunction "Card_Detect_10") (pintype "passive"))
      (node (ref "U1") (pin "46") (pinfunction "PF1_46") (pintype "bidirectional"))
    )
    (net (code "39") (name "Net-(SD-DI)") (class "Default")
      (node (ref "SD") (pin "2") (pinfunction "DI_2") (pintype "input"))
      (node (ref "U1") (pin "50") (pinfunction "PF5_50") (pintype "bidirectional"))
    )
    (net (code "40") (name "Net-(SD-DO)") (class "Default")
      (node (ref "SD") (pin "7") (pinfunction "DO_7") (pintype "output"))
      (node (ref "U1") (pin "51") (pinfunction "PF6_51") (pintype "bidirectional"))
    )
    (net (code "41") (name "Net-(SD-WR_Protected)") (class "Default")
      (node (ref "SD") (pin "11") (pinfunction "WR_Protected_11") (pintype "passive"))
      (node (ref "U1") (pin "45") (pinfunction "PF0_45") (pintype "bidirectional"))
    )
    (net (code "42") (name "Net-(SD-~CS)") (class "Default")
      (node (ref "SD") (pin "1") (pinfunction "~CS_1") (pintype "input"))
      (node (ref "U1") (pin "49") (pinfunction "PF4_49") (pintype "bidirectional"))
    )
    (net (code "43") (name "Net-(U1-AVCC_-_A)") (class "Default")
      (node (ref "C2") (pin "2") (pinfunction "2_2") (pintype "passive"))
      (node (ref "L1") (pin "1") (pinfunction "1_1") (pintype "passive"))
      (node (ref "U1") (pin "94") (pinfunction "AVCC_-_A_94") (pintype "power_in"))
    )
    (net (code "44") (name "Net-(U1-AVCC_-_B)") (class "Default")
      (node (ref "C3") (pin "2") (pinfunction "2_2") (pintype "passive"))
      (node (ref "L2") (pin "1") (pinfunction "1_1") (pintype "passive"))
      (node (ref "U1") (pin "4") (pinfunction "AVCC_-_B_4") (pintype "power_in"))
    )
    (net (code "45") (name "Net-(U1-PA3)") (class "Default")
      (node (ref "U1") (pin "98") (pinfunction "PA3_98") (pintype "bidirectional"))
      (node (ref "U4") (pin "3") (pinfunction "IN+_3") (pintype "input"))
    )
    (net (code "46") (name "Net-(U1-PB3)") (class "Default")
      (node (ref "U1") (pin "8") (pinfunction "PB3_8") (pintype "bidirectional"))
      (node (ref "U4") (pin "5") (pinfunction "IN+_5") (pintype "input"))
    )
    (net (code "47") (name "Net-(U1-PD0)") (class "Default")
      (node (ref "Keypad") (pin "1") (pinfunction "1_1") (pintype "passive"))
      (node (ref "U1") (pin "25") (pinfunction "PD0_25") (pintype "bidirectional"))
    )
    (net (code "48") (name "Net-(U1-PD1)") (class "Default")
      (node (ref "Keypad") (pin "2") (pinfunction "2_2") (pintype "passive"))
      (node (ref "U1") (pin "26") (pinfunction "PD1_26") (pintype "bidirectional"))
    )
    (net (code "49") (name "Net-(U1-PD2)") (class "Default")
      (node (ref "Keypad") (pin "3") (pinfunction "3_3") (pintype "passive"))
      (node (ref "U1") (pin "27") (pinfunction "PD2_27") (pintype "bidirectional"))
    )
    (net (code "50") (name "Net-(U1-PD3)") (class "Default")
      (node (ref "Keypad") (pin "4") (pinfunction "4_4") (pintype "passive"))
      (node (ref "U1") (pin "28") (pinfunction "PD3_28") (pintype "bidirectional"))
    )
    (net (code "51") (name "Net-(U1-PD4)") (class "Default")
      (node (ref "Keypad") (pin "5") (pinfunction "5_5") (pintype "passive"))
      (node (ref "U1") (pin "29") (pinfunction "PD4_29") (pintype "bidirectional"))
    )
    (net (code "52") (name "Net-(U1-PD5)") (class "Default")
      (node (ref "Keypad") (pin "6") (pinfunction "6_6") (pintype "passive"))
      (node (ref "U1") (pin "30") (pinfunction "PD5_30") (pintype "bidirectional"))
    )
    (net (code "53") (name "Net-(U1-PD6)") (class "Default")
      (node (ref "Keypad") (pin "7") (pinfunction "7_7") (pintype "passive"))
      (node (ref "U1") (pin "31") (pinfunction "PD6_31") (pintype "bidirectional"))
    )
    (net (code "54") (name "Net-(U1-PD7)") (class "Default")
      (node (ref "Keypad") (pin "8") (pinfunction "8_8") (pintype "passive"))
      (node (ref "U1") (pin "32") (pinfunction "PD7_32") (pintype "bidirectional"))
    )
    (net (code "55") (name "Net-(U1-PE3)") (class "Default")
      (node (ref "S2") (pin "1") (pinfunction "1_1") (pintype "passive"))
      (node (ref "U1") (pin "38") (pinfunction "PE3_38") (pintype "bidirectional"))
    )
    (net (code "56") (name "Net-(U1-PH0)") (class "Default")
      (node (ref "U1") (pin "55") (pinfunction "PH0_55") (pintype "bidirectional"))
      (node (ref "U6") (pin "15") (pinfunction "BIT_12_(LSB)_15") (pintype "input"))
    )
    (net (code "57") (name "Net-(U1-PH1)") (class "Default")
      (node (ref "U1") (pin "56") (pinfunction "PH1_56") (pintype "bidirectional"))
      (node (ref "U6") (pin "14") (pinfunction "BIT_11_14") (pintype "input"))
    )
    (net (code "58") (name "Net-(U1-PH2)") (class "Default")
      (node (ref "U1") (pin "57") (pinfunction "PH2_57") (pintype "bidirectional"))
      (node (ref "U6") (pin "13") (pinfunction "BIT_10_13") (pintype "input"))
    )
    (net (code "59") (name "Net-(U1-PH3)") (class "Default")
      (node (ref "U1") (pin "58") (pinfunction "PH3_58") (pintype "bidirectional"))
      (node (ref "U6") (pin "12") (pinfunction "BIT_9_12") (pintype "input"))
    )
    (net (code "60") (name "Net-(U1-PH4)") (class "Default")
      (node (ref "U1") (pin "59") (pinfunction "PH4_59") (pintype "bidirectional"))
      (node (ref "U6") (pin "11") (pinfunction "BIT_8_11") (pintype "input"))
    )
    (net (code "61") (name "Net-(U1-PH5)") (class "Default")
      (node (ref "U1") (pin "60") (pinfunction "PH5_60") (pintype "bidirectional"))
      (node (ref "U6") (pin "10") (pinfunction "BIT_7_10") (pintype "input"))
    )
    (net (code "62") (name "Net-(U1-PH6)") (class "Default")
      (node (ref "U1") (pin "61") (pinfunction "PH6_61") (pintype "bidirectional"))
      (node (ref "U6") (pin "9") (pinfunction "BIT_6_9") (pintype "input"))
    )
    (net (code "63") (name "Net-(U1-PH7)") (class "Default")
      (node (ref "U1") (pin "62") (pinfunction "PH7_62") (pintype "bidirectional"))
      (node (ref "U6") (pin "8") (pinfunction "BIT_5_8") (pintype "input"))
    )
    (net (code "64") (name "Net-(U1-PJ0)") (class "Default")
      (node (ref "U1") (pin "65") (pinfunction "PJ0_65") (pintype "bidirectional"))
      (node (ref "U6") (pin "7") (pinfunction "BIT_4_7") (pintype "input"))
    )
    (net (code "65") (name "Net-(U1-PJ1)") (class "Default")
      (node (ref "U1") (pin "66") (pinfunction "PJ1_66") (pintype "bidirectional"))
      (node (ref "U6") (pin "6") (pinfunction "BIT_3_6") (pintype "input"))
    )
    (net (code "66") (name "Net-(U1-PJ2)") (class "Default")
      (node (ref "U1") (pin "67") (pinfunction "PJ2_67") (pintype "bidirectional"))
      (node (ref "U6") (pin "5") (pinfunction "BIT_2_5") (pintype "input"))
    )
    (net (code "67") (name "Net-(U1-PJ3)") (class "Default")
      (node (ref "U1") (pin "68") (pinfunction "PJ3_68") (pintype "bidirectional"))
      (node (ref "U6") (pin "4") (pinfunction "BIT_1_(MSB)_4") (pintype "input"))
    )
    (net (code "68") (name "Net-(U1-PJ4)") (class "Default")
      (node (ref "U1") (pin "69") (pinfunction "PJ4_69") (pintype "bidirectional"))
      (node (ref "U5") (pin "15") (pinfunction "BIT_12_(LSB)_15") (pintype "input"))
    )
    (net (code "69") (name "Net-(U1-PJ5)") (class "Default")
      (node (ref "U1") (pin "70") (pinfunction "PJ5_70") (pintype "bidirectional"))
      (node (ref "U5") (pin "14") (pinfunction "BIT_11_14") (pintype "input"))
    )
    (net (code "70") (name "Net-(U1-PJ6)") (class "Default")
      (node (ref "U1") (pin "71") (pinfunction "PJ6_71") (pintype "bidirectional"))
      (node (ref "U5") (pin "13") (pinfunction "BIT_10_13") (pintype "input"))
    )
    (net (code "71") (name "Net-(U1-PJ7)") (class "Default")
      (node (ref "U1") (pin "72") (pinfunction "PJ7_72") (pintype "bidirectional"))
      (node (ref "U5") (pin "12") (pinfunction "BIT_9_12") (pintype "input"))
    )
    (net (code "72") (name "Net-(U1-PK0)") (class "Default")
      (node (ref "U1") (pin "75") (pinfunction "PK0_75") (pintype "bidirectional"))
      (node (ref "U5") (pin "11") (pinfunction "BIT_8_11") (pintype "input"))
    )
    (net (code "73") (name "Net-(U1-PK1)") (class "Default")
      (node (ref "U1") (pin "76") (pinfunction "PK1_76") (pintype "bidirectional"))
      (node (ref "U5") (pin "10") (pinfunction "BIT_7_10") (pintype "input"))
    )
    (net (code "74") (name "Net-(U1-PK2)") (class "Default")
      (node (ref "U1") (pin "77") (pinfunction "PK2_77") (pintype "bidirectional"))
      (node (ref "U5") (pin "9") (pinfunction "BIT_6_9") (pintype "input"))
    )
    (net (code "75") (name "Net-(U1-PK3)") (class "Default")
      (node (ref "U1") (pin "78") (pinfunction "PK3_78") (pintype "bidirectional"))
      (node (ref "U5") (pin "8") (pinfunction "BIT_5_8") (pintype "input"))
    )
    (net (code "76") (name "Net-(U1-PK4)") (class "Default")
      (node (ref "U1") (pin "79") (pinfunction "PK4_79") (pintype "bidirectional"))
      (node (ref "U5") (pin "7") (pinfunction "BIT_4_7") (pintype "input"))
    )
    (net (code "77") (name "Net-(U1-PK5)") (class "Default")
      (node (ref "U1") (pin "80") (pinfunction "PK5_80") (pintype "bidirectional"))
      (node (ref "U5") (pin "6") (pinfunction "BIT_3_6") (pintype "input"))
    )
    (net (code "78") (name "Net-(U1-PK6)") (class "Default")
      (node (ref "U1") (pin "81") (pinfunction "PK6_81") (pintype "bidirectional"))
      (node (ref "U5") (pin "5") (pinfunction "BIT_2_5") (pintype "input"))
    )
    (net (code "79") (name "Net-(U1-PK7)") (class "Default")
      (node (ref "U1") (pin "82") (pinfunction "PK7_82") (pintype "bidirectional"))
      (node (ref "U5") (pin "4") (pinfunction "BIT_1_(MSB)_4") (pintype "input"))
    )
    (net (code "80") (name "Net-(U2-10.0V)") (class "Default")
      (node (ref "C23") (pin "2") (pinfunction "2_2") (pintype "passive"))
      (node (ref "R1") (pin "1") (pinfunction "1_1") (pintype "passive"))
      (node (ref "U2") (pin "1") (pinfunction "10.0V_1") (pintype "power_in"))
      (node (ref "U3") (pin "5") (pinfunction "IN+_5") (pintype "input"))
    )
    (net (code "81") (name "Net-(U2-CAP)") (class "Default")
      (node (ref "C5") (pin "2") (pinfunction "2_2") (pintype "passive"))
      (node (ref "U2") (pin "7") (pinfunction "CAP_7") (pintype "passive"))
    )
    (net (code "82") (name "Net-(U2-STB)") (class "Default")
      (node (ref "C5") (pin "1") (pinfunction "1_1") (pintype "passive"))
      (node (ref "U2") (pin "5") (pinfunction "STB_5") (pintype "input"))
    )
    (net (code "83") (name "Net-(U3A-IN-)") (class "Default")
      (node (ref "L3") (pin "2") (pinfunction "2_2") (pintype "passive"))
      (node (ref "U3") (pin "1") (pinfunction "OUT_1") (pintype "output"))
      (node (ref "U3") (pin "2") (pinfunction "IN-_2") (pintype "input"))
    )
    (net (code "84") (name "Net-(U4B-IN-)") (class "Default")
      (node (ref "R5") (pin "2") (pinfunction "2_2") (pintype "passive"))
      (node (ref "R6") (pin "1") (pinfunction "1_1") (pintype "passive"))
      (node (ref "U4") (pin "6") (pinfunction "IN-_6") (pintype "input"))
    )
    (net (code "85") (name "Net-(U5-Iout1)") (class "Default")
      (node (ref "U5") (pin "1") (pinfunction "Iout1_1") (pintype "output"))
      (node (ref "U7") (pin "2") (pinfunction "IN-_2") (pintype "input"))
    )
    (net (code "86") (name "Net-(U6-Iout1)") (class "Default")
      (node (ref "U6") (pin "1") (pinfunction "Iout1_1") (pintype "output"))
      (node (ref "U7") (pin "6") (pinfunction "IN-_6") (pintype "input"))
    )
    (net (code "87") (name "Net-(U8-C1+)") (class "Default")
      (node (ref "C32") (pin "2") (pinfunction "2_2") (pintype "passive"))
      (node (ref "U8") (pin "1") (pinfunction "C1+_1") (pintype "passive"))
    )
    (net (code "88") (name "Net-(U8-C1-)") (class "Default")
      (node (ref "C32") (pin "1") (pinfunction "1_1") (pintype "passive"))
      (node (ref "U8") (pin "3") (pinfunction "C1-_3") (pintype "passive"))
    )
    (net (code "89") (name "Net-(U8-C2+)") (class "Default")
      (node (ref "C25") (pin "2") (pinfunction "2_2") (pintype "passive"))
      (node (ref "U8") (pin "4") (pinfunction "C2+_4") (pintype "passive"))
    )
    (net (code "90") (name "Net-(U8-C2-)") (class "Default")
      (node (ref "C25") (pin "1") (pinfunction "1_1") (pintype "passive"))
      (node (ref "U8") (pin "5") (pinfunction "C2-_5") (pintype "passive"))
    )
    (net (code "91") (name "Net-(U8-R1IN)") (class "Default")
      (node (ref "U8") (pin "13") (pinfunction "R1IN_13") (pintype "input"))
      (node (ref "USART") (pin "3") (pinfunction "3_3") (pintype "passive"))
    )
    (net (code "92") (name "Net-(U8-R1OUT)") (class "Default")
      (node (ref "R10") (pin "1") (pinfunction "1_1") (pintype "passive"))
      (node (ref "U8") (pin "12") (pinfunction "R1OUT_12") (pintype "output"))
    )
    (net (code "93") (name "Net-(U8-T1OUT)") (class "Default")
      (node (ref "U8") (pin "14") (pinfunction "T1OUT_14") (pintype "output"))
      (node (ref "USART") (pin "2") (pinfunction "2_2") (pintype "passive"))
    )
    (net (code "94") (name "Net-(U8-VDD)") (class "Default")
      (node (ref "C33") (pin "2") (pinfunction "2_2") (pintype "passive"))
      (node (ref "U8") (pin "2") (pinfunction "VDD_2") (pintype "power_in"))
    )
    (net (code "95") (name "Net-(U8-VEE)") (class "Default")
      (node (ref "C24") (pin "1") (pinfunction "1_1") (pintype "passive"))
      (node (ref "U8") (pin "6") (pinfunction "VEE_6") (pintype "power_in"))
    )
    (net (code "96") (name "Net-(U11-OUT)") (class "Default")
      (node (ref "C38") (pin "2") (pinfunction "2_2") (pintype "passive"))
      (node (ref "U11") (pin "3") (pinfunction "OUT_3") (pintype "power_in"))
      (node (ref "U12") (pin "3") (pinfunction "IN_3") (pintype "power_in"))
    )
    (net (code "97") (name "unconnected-(LCD1-D0-Pad7)") (class "Default")
      (node (ref "LCD1") (pin "7") (pinfunction "D0_7") (pintype "bidirectional"))
    )
    (net (code "98") (name "unconnected-(LCD1-D1-Pad8)") (class "Default")
      (node (ref "LCD1") (pin "8") (pinfunction "D1_8") (pintype "bidirectional"))
    )
    (net (code "99") (name "unconnected-(LCD1-D2-Pad9)") (class "Default")
      (node (ref "LCD1") (pin "9") (pinfunction "D2_9") (pintype "bidirectional"))
    )
    (net (code "100") (name "unconnected-(LCD1-D3-Pad10)") (class "Default")
      (node (ref "LCD1") (pin "10") (pinfunction "D3_10") (pintype "bidirectional"))
    )
    (net (code "101") (name "unconnected-(LCD1-H1-Pad17)") (class "Default")
      (node (ref "LCD1") (pin "17") (pinfunction "H1_17") (pintype "passive"))
    )
    (net (code "102") (name "unconnected-(LCD1-H2-Pad18)") (class "Default")
      (node (ref "LCD1") (pin "18") (pinfunction "H2_18") (pintype "passive"))
    )
    (net (code "103") (name "unconnected-(LCD1-H3-Pad19)") (class "Default")
      (node (ref "LCD1") (pin "19") (pinfunction "H3_19") (pintype "passive"))
    )
    (net (code "104") (name "unconnected-(LCD1-H4-Pad20)") (class "Default")
      (node (ref "LCD1") (pin "20") (pinfunction "H4_20") (pintype "passive"))
    )
    (net (code "105") (name "unconnected-(SD-Majid-Pad8)") (class "Default")
      (node (ref "SD") (pin "8") (pinfunction "Majid_8") (pintype "tri_state"))
    )
    (net (code "106") (name "unconnected-(U1-PA1-Pad96)") (class "Default")
      (node (ref "U1") (pin "96") (pinfunction "PA1_96") (pintype "bidirectional"))
    )
    (net (code "107") (name "unconnected-(U1-PA4-Pad99)") (class "Default")
      (node (ref "U1") (pin "99") (pinfunction "PA4_99") (pintype "bidirectional"))
    )
    (net (code "108") (name "unconnected-(U1-PA6-Pad1)") (class "Default")
      (node (ref "U1") (pin "1") (pinfunction "PA6_1") (pintype "bidirectional"))
    )
    (net (code "109") (name "unconnected-(U1-PA7-Pad2)") (class "Default")
      (node (ref "U1") (pin "2") (pinfunction "PA7_2") (pintype "bidirectional"))
    )
    (net (code "110") (name "unconnected-(U1-PB0-Pad5)") (class "Default")
      (node (ref "U1") (pin "5") (pinfunction "PB0_5") (pintype "bidirectional"))
    )
    (net (code "111") (name "unconnected-(U1-PB1-Pad6)") (class "Default")
      (node (ref "U1") (pin "6") (pinfunction "PB1_6") (pintype "bidirectional"))
    )
    (net (code "112") (name "unconnected-(U1-PB2-Pad7)") (class "Default")
      (node (ref "U1") (pin "7") (pinfunction "PB2_7") (pintype "bidirectional"))
    )
    (net (code "113") (name "unconnected-(U1-PB4-Pad9)") (class "Default")
      (node (ref "U1") (pin "9") (pinfunction "PB4_9") (pintype "bidirectional"))
    )
    (net (code "114") (name "unconnected-(U1-PB5-Pad10)") (class "Default")
      (node (ref "U1") (pin "10") (pinfunction "PB5_10") (pintype "bidirectional"))
    )
    (net (code "115") (name "unconnected-(U1-PB6-Pad11)") (class "Default")
      (node (ref "U1") (pin "11") (pinfunction "PB6_11") (pintype "bidirectional"))
    )
    (net (code "116") (name "unconnected-(U1-PB7-Pad12)") (class "Default")
      (node (ref "U1") (pin "12") (pinfunction "PB7_12") (pintype "bidirectional"))
    )
    (net (code "117") (name "unconnected-(U1-PC0-Pad15)") (class "Default")
      (node (ref "U1") (pin "15") (pinfunction "PC0_15") (pintype "bidirectional"))
    )
    (net (code "118") (name "unconnected-(U1-PC1-Pad16)") (class "Default")
      (node (ref "U1") (pin "16") (pinfunction "PC1_16") (pintype "bidirectional"))
    )
    (net (code "119") (name "unconnected-(U1-PC2-Pad17)") (class "Default")
      (node (ref "U1") (pin "17") (pinfunction "PC2_17") (pintype "bidirectional"))
    )
    (net (code "120") (name "unconnected-(U1-PC3-Pad18)") (class "Default")
      (node (ref "U1") (pin "18") (pinfunction "PC3_18") (pintype "bidirectional"))
    )
    (net (code "121") (name "unconnected-(U1-PC4-Pad19)") (class "Default")
      (node (ref "U1") (pin "19") (pinfunction "PC4_19") (pintype "bidirectional"))
    )
    (net (code "122") (name "unconnected-(U1-PC5-Pad20)") (class "Default")
      (node (ref "U1") (pin "20") (pinfunction "PC5_20") (pintype "bidirectional"))
    )
    (net (code "123") (name "unconnected-(U1-PC6-Pad21)") (class "Default")
      (node (ref "U1") (pin "21") (pinfunction "PC6_21") (pintype "bidirectional"))
    )
    (net (code "124") (name "unconnected-(U1-PC7-Pad22)") (class "Default")
      (node (ref "U1") (pin "22") (pinfunction "PC7_22") (pintype "bidirectional"))
    )
    (net (code "125") (name "unconnected-(U1-PE1-Pad36)") (class "Default")
      (node (ref "U1") (pin "36") (pinfunction "PE1_36") (pintype "bidirectional"))
    )
    (net (code "126") (name "unconnected-(U1-PQ0-Pad85)") (class "Default")
      (node (ref "U1") (pin "85") (pinfunction "PQ0_85") (pintype "bidirectional"))
    )
    (net (code "127") (name "unconnected-(U1-PQ1-Pad86)") (class "Default")
      (node (ref "U1") (pin "86") (pinfunction "PQ1_86") (pintype "bidirectional"))
    )
    (net (code "128") (name "unconnected-(U1-PQ2-Pad87)") (class "Default")
      (node (ref "U1") (pin "87") (pinfunction "PQ2_87") (pintype "bidirectional"))
    )
    (net (code "129") (name "unconnected-(U1-PQ3-Pad88)") (class "Default")
      (node (ref "U1") (pin "88") (pinfunction "PQ3_88") (pintype "bidirectional"))
    )
    (net (code "130") (name "unconnected-(U2-2.5V-Pad3)") (class "Default")
      (node (ref "U2") (pin "3") (pinfunction "2.5V_3") (pintype "power_in"))
    )
    (net (code "131") (name "unconnected-(U2-5.0V-Pad2)") (class "Default")
      (node (ref "U2") (pin "2") (pinfunction "5.0V_2") (pintype "power_in"))
    )
    (net (code "132") (name "unconnected-(U2-VBG-Pad6)") (class "Default")
      (node (ref "U2") (pin "6") (pinfunction "VBG_6") (pintype "passive"))
    )
    (net (code "133") (name "unconnected-(U3A-V+-Pad8)") (class "Default")
      (node (ref "U3") (pin "8") (pinfunction "V+_8") (pintype "power_in"))
    )
    (net (code "134") (name "unconnected-(U3A-V--Pad4)") (class "Default")
      (node (ref "U3") (pin "4") (pinfunction "V-_4") (pintype "power_in"))
    )
    (net (code "135") (name "unconnected-(U4A-V+-Pad8)") (class "Default")
      (node (ref "U4") (pin "8") (pinfunction "V+_8") (pintype "power_in"))
    )
    (net (code "136") (name "unconnected-(U4B-V--Pad4)") (class "Default")
      (node (ref "U4") (pin "4") (pinfunction "V-_4") (pintype "power_in"))
    )
    (net (code "137") (name "unconnected-(U7B-V+-Pad8)") (class "Default")
      (node (ref "U7") (pin "8") (pinfunction "V+_8") (pintype "power_in"))
    )
    (net (code "138") (name "unconnected-(U7B-V--Pad4)") (class "Default")
      (node (ref "U7") (pin "4") (pinfunction "V-_4") (pintype "power_in"))
    )
    (net (code "139") (name "unconnected-(U8-R2IN-Pad8)") (class "Default")
      (node (ref "U8") (pin "8") (pinfunction "R2IN_8") (pintype "input"))
    )
    (net (code "140") (name "unconnected-(U8-R2OUT-Pad9)") (class "Default")
      (node (ref "U8") (pin "9") (pinfunction "R2OUT_9") (pintype "output"))
    )
    (net (code "141") (name "unconnected-(U8-T2IN-Pad10)") (class "Default")
      (node (ref "U8") (pin "10") (pinfunction "T2IN_10") (pintype "input"))
    )
    (net (code "142") (name "unconnected-(U8-T2OUT-Pad7)") (class "Default")
      (node (ref "U8") (pin "7") (pinfunction "T2OUT_7") (pintype "output"))
    )
  )
)
